# WaterSens_V1-0.net
KiCad netlist of a schematic drawn in EAGLE
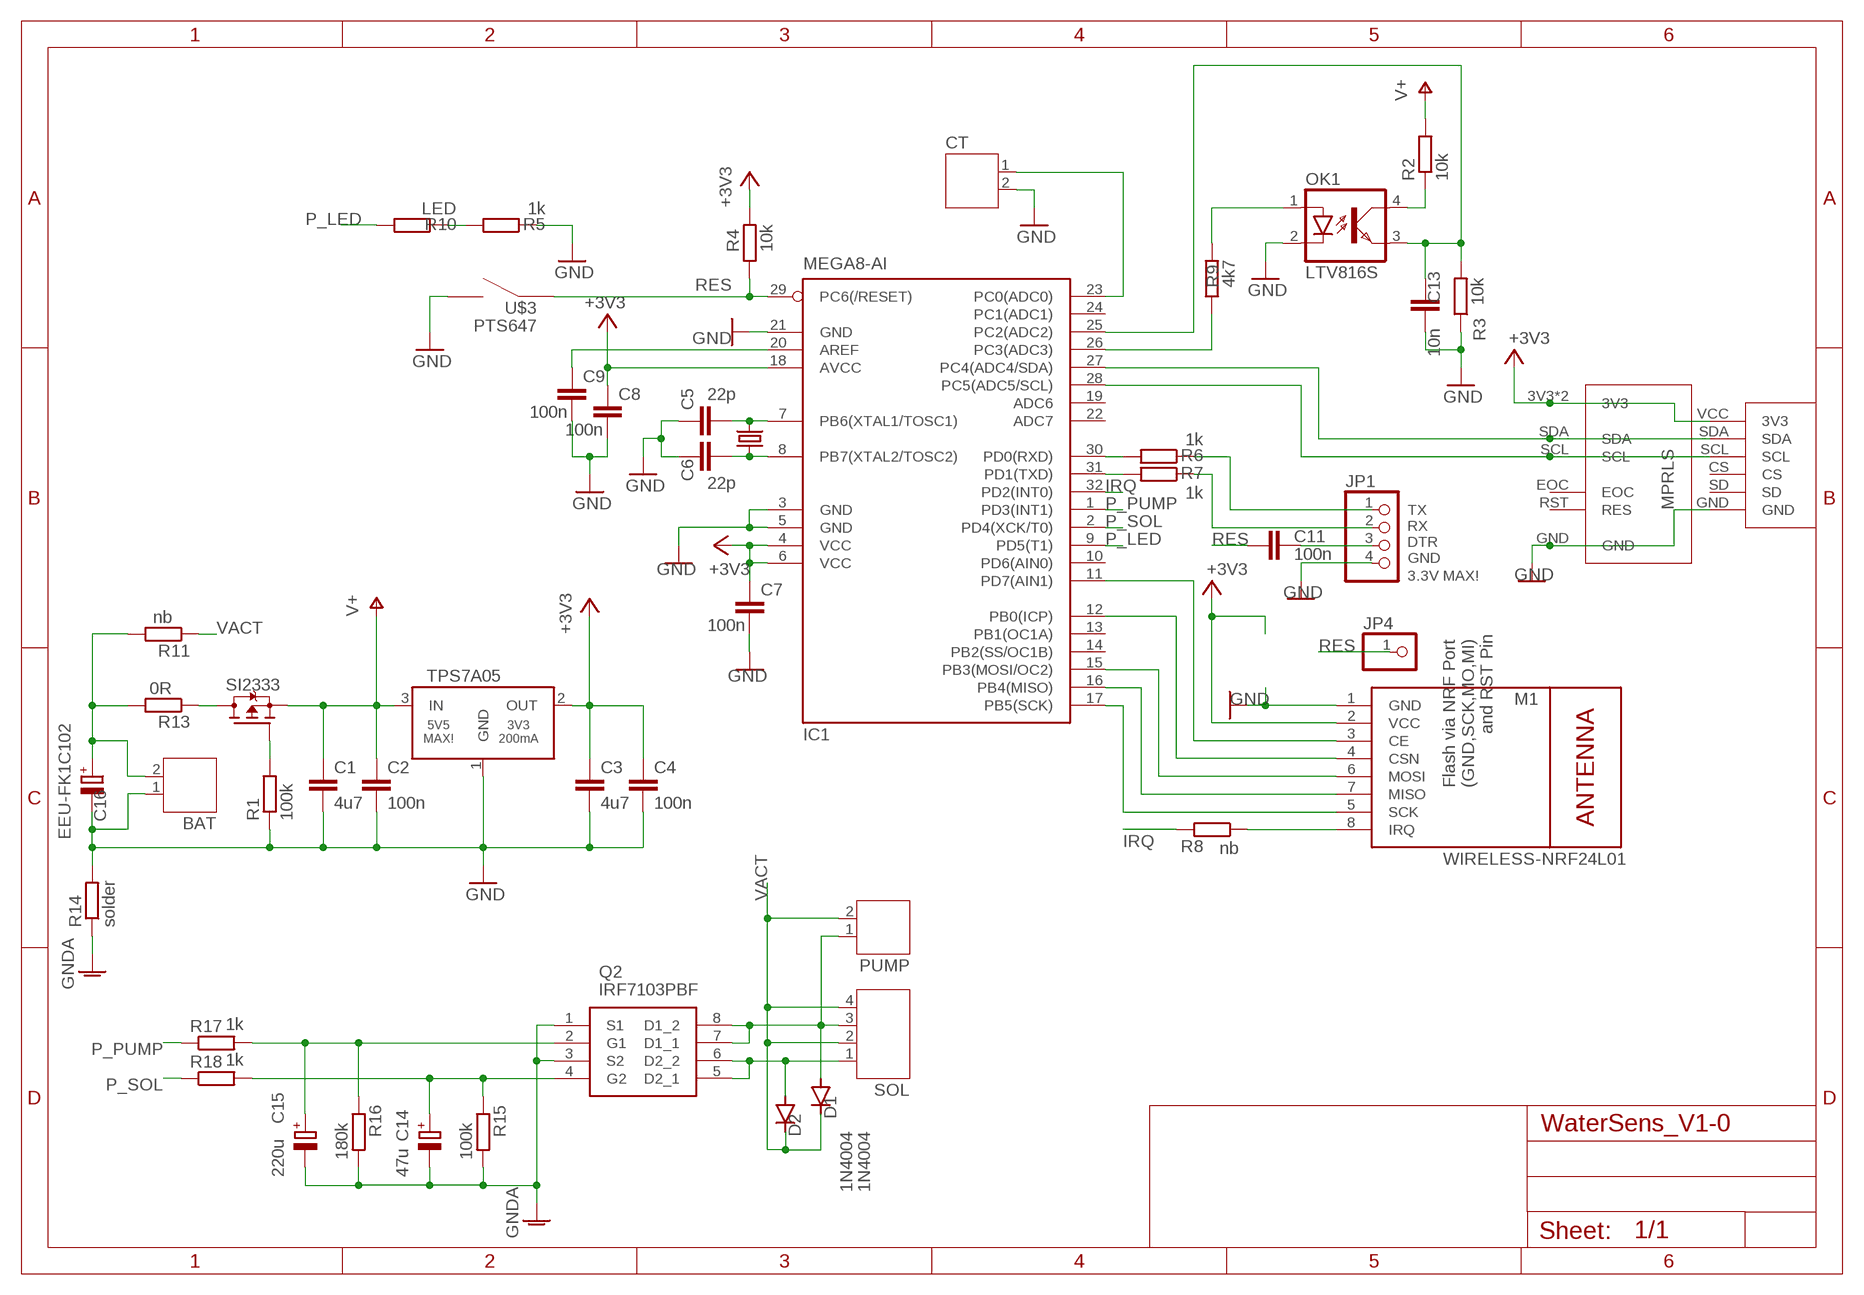
[diagram p0: schematic, sheet 1]

(export (version "E")
  (design (tool "Eeschema 10.0.6"))
  (components
    (comp (ref "BAT")
      (value "JST-PH2")
      (footprint "eagle-import:JST-PH2")
      (libsource (lib "eagle-import") (part "JST-PH2"))
    )
    (comp (ref "C1")
      (value "4u7")
      (footprint "eagle-import:C0805")
      (libsource (lib "eagle-import") (part "C-EUC0805"))
    )
    (comp (ref "C2")
      (value "100n")
      (footprint "eagle-import:C0805")
      (libsource (lib "eagle-import") (part "C-EUC0805"))
    )
    (comp (ref "C3")
      (value "4u7")
      (footprint "eagle-import:C0805")
      (libsource (lib "eagle-import") (part "C-EUC0805"))
    )
    (comp (ref "C4")
      (value "100n")
      (footprint "eagle-import:C0805")
      (libsource (lib "eagle-import") (part "C-EUC0805"))
    )
    (comp (ref "C5")
      (value "22p")
      (footprint "eagle-import:C0805")
      (libsource (lib "eagle-import") (part "C-EUC0805"))
    )
    (comp (ref "C6")
      (value "22p")
      (footprint "eagle-import:C0805")
      (libsource (lib "eagle-import") (part "C-EUC0805"))
    )
    (comp (ref "C7")
      (value "100n")
      (footprint "eagle-import:C0805")
      (libsource (lib "eagle-import") (part "C-EUC0805"))
    )
    (comp (ref "C8")
      (value "100n")
      (footprint "eagle-import:C0805")
      (libsource (lib "eagle-import") (part "C-EUC0805"))
    )
    (comp (ref "C9")
      (value "100n")
      (footprint "eagle-import:C0805")
      (libsource (lib "eagle-import") (part "C-EUC0805"))
    )
    (comp (ref "C11")
      (value "100n")
      (footprint "eagle-import:C0805")
      (libsource (lib "eagle-import") (part "C-EUC0805"))
    )
    (comp (ref "C13")
      (value "10n")
      (footprint "eagle-import:C0805")
      (libsource (lib "eagle-import") (part "C-EUC0805"))
    )
    (comp (ref "C14")
      (value "47u")
      (footprint "eagle-import:E1,8-4")
      (libsource (lib "eagle-import") (part "CPOL-EUE1.8-4"))
    )
    (comp (ref "C15")
      (value "220u")
      (footprint "eagle-import:E2,5-6E")
      (libsource (lib "eagle-import") (part "CPOL-EUE2,5-6E"))
    )
    (comp (ref "C16")
      (value "EEU-FK1C102")
      (footprint "eagle-import:E5-10,5")
      (libsource (lib "eagle-import") (part "CPOL-EUE5-10.5"))
    )
    (comp (ref "CT")
      (value "JST-PH2")
      (footprint "eagle-import:JST-PH2")
      (libsource (lib "eagle-import") (part "JST-PH2"))
    )
    (comp (ref "D1")
      (value "1N4004")
      (footprint "eagle-import:DO41-10")
      (libsource (lib "eagle-import") (part "1N4004"))
    )
    (comp (ref "D2")
      (value "1N4004")
      (footprint "eagle-import:DO41-10")
      (libsource (lib "eagle-import") (part "1N4004"))
    )
    (comp (ref "IC1")
      (value "MEGA8-AI")
      (footprint "eagle-import:TQFP32-08")
      (fields (field (name "MPN") "ATMEGA8-16AU"))
      (libsource (lib "eagle-import") (part "MEGA8-AI"))
    )
    (comp (ref "JP1")
      (value "PINHD-1X4")
      (footprint "eagle-import:1X04")
      (libsource (lib "eagle-import") (part "PINHD-1X4"))
    )
    (comp (ref "JP4")
      (value "PINHD-1X1")
      (footprint "eagle-import:1X01")
      (libsource (lib "eagle-import") (part "PINHD-1X1"))
    )
    (comp (ref "M1")
      (value "WIRELESS-NRF24L01")
      (footprint "eagle-import:WIRELESS-NRF24L01")
      (libsource (lib "eagle-import") (part "WIRELESS-NRF24L01"))
    )
    (comp (ref "OK1")
      (value "LTV816S")
      (footprint "eagle-import:DIL4-SMD")
      (libsource (lib "eagle-import") (part "LTV816S"))
    )
    (comp (ref "PUMP")
      (value "JST-PH2")
      (footprint "eagle-import:JST-PH2")
      (libsource (lib "eagle-import") (part "JST-PH2"))
    )
    (comp (ref "Q1")
      (value "CRYSTALHC49UP")
      (footprint "eagle-import:HC49UP")
      (libsource (lib "eagle-import") (part "CRYSTALHC49UP"))
    )
    (comp (ref "Q2")
      (value "IRF7103PBF")
      (footprint "eagle-import:SOIC127P600X175-8N")
      (libsource (lib "eagle-import") (part "IRF7103PBF"))
    )
    (comp (ref "R1")
      (value "100k")
      (footprint "eagle-import:R0805")
      (libsource (lib "eagle-import") (part "R-EU_R0805"))
    )
    (comp (ref "R2")
      (value "10k")
      (footprint "eagle-import:R0805")
      (libsource (lib "eagle-import") (part "R-EU_R0805"))
    )
    (comp (ref "R3")
      (value "10k")
      (footprint "eagle-import:R0805")
      (libsource (lib "eagle-import") (part "R-EU_R0805"))
    )
    (comp (ref "R4")
      (value "10k")
      (footprint "eagle-import:R0805")
      (libsource (lib "eagle-import") (part "R-EU_R0805"))
    )
    (comp (ref "R5")
      (value "1k")
      (footprint "eagle-import:R0805")
      (libsource (lib "eagle-import") (part "R-EU_R0805"))
    )
    (comp (ref "R6")
      (value "1k")
      (footprint "eagle-import:R0805")
      (libsource (lib "eagle-import") (part "R-EU_R0805"))
    )
    (comp (ref "R7")
      (value "1k")
      (footprint "eagle-import:R0805")
      (libsource (lib "eagle-import") (part "R-EU_R0805"))
    )
    (comp (ref "R8")
      (value "nb")
      (footprint "eagle-import:R0805")
      (libsource (lib "eagle-import") (part "R-EU_R0805"))
    )
    (comp (ref "R9")
      (value "4k7")
      (footprint "eagle-import:R0805")
      (libsource (lib "eagle-import") (part "R-EU_R0805"))
    )
    (comp (ref "R10")
      (value "LED")
      (footprint "eagle-import:R0805")
      (libsource (lib "eagle-import") (part "R-EU_R0805"))
    )
    (comp (ref "R11")
      (value "nb")
      (footprint "eagle-import:R0805")
      (libsource (lib "eagle-import") (part "R-EU_R0805"))
    )
    (comp (ref "R13")
      (value "0R")
      (footprint "eagle-import:R0805")
      (libsource (lib "eagle-import") (part "R-EU_R0805"))
    )
    (comp (ref "R14")
      (value "solder")
      (footprint "eagle-import:R0805")
      (libsource (lib "eagle-import") (part "R-EU_R0805"))
    )
    (comp (ref "R15")
      (value "100k")
      (footprint "eagle-import:R0805")
      (libsource (lib "eagle-import") (part "R-EU_R0805"))
    )
    (comp (ref "R16")
      (value "180k")
      (footprint "eagle-import:R0805")
      (libsource (lib "eagle-import") (part "R-EU_R0805"))
    )
    (comp (ref "R17")
      (value "1k")
      (footprint "eagle-import:R0805")
      (libsource (lib "eagle-import") (part "R-EU_R0805"))
    )
    (comp (ref "R18")
      (value "1k")
      (footprint "eagle-import:R0805")
      (libsource (lib "eagle-import") (part "R-EU_R0805"))
    )
    (comp (ref "SOL")
      (value "JST-PH4")
      (footprint "eagle-import:JST-PH4")
      (libsource (lib "eagle-import") (part "JST-PH4"))
    )
    (comp (ref "U$1")
      (value "MPRLS_ADA")
      (footprint "eagle-import:MPRLS_ADA")
      (libsource (lib "eagle-import") (part "MPRLS_ADA"))
    )
    (comp (ref "U$2")
      (value "TEMP-HUM-PRES-BME280-3V3")
      (footprint "eagle-import:TEMP-HUM-PRES-BME280-3V3")
      (libsource (lib "eagle-import") (part "TEMP-HUM-PRES-BME280-3V3"))
    )
    (comp (ref "U$3")
      (value "PTS647")
      (footprint "eagle-import:PTS647")
      (libsource (lib "eagle-import") (part "PTS647"))
    )
    (comp (ref "U$5")
      (value "TPS7A05")
      (footprint "eagle-import:SOT23")
      (libsource (lib "eagle-import") (part "TPS7A05"))
    )
    (comp (ref "U$6")
      (value "SI2333")
      (footprint "eagle-import:SOT23")
      (libsource (lib "eagle-import") (part "SI2333"))
    )
  )
  (nets
    (net (code "1") (name "+3V3") (class "Default")
      (node (ref "C3") (pin "1") (pinfunction "1_1") (pintype "passive"))
      (node (ref "C4") (pin "1") (pinfunction "1_1") (pintype "passive"))
      (node (ref "C7") (pin "1") (pinfunction "1_1") (pintype "passive"))
      (node (ref "C8") (pin "1") (pinfunction "1_1") (pintype "passive"))
      (node (ref "IC1") (pin "18") (pinfunction "AVCC_18") (pintype "power_in"))
      (node (ref "IC1") (pin "4") (pinfunction "VCC_4") (pintype "power_in"))
      (node (ref "IC1") (pin "6") (pinfunction "VCC_6") (pintype "power_in"))
      (node (ref "M1") (pin "2") (pinfunction "VCC_2") (pintype "power_in"))
      (node (ref "R4") (pin "2") (pinfunction "2_2") (pintype "passive"))
      (node (ref "U$1") (pin "3V3") (pinfunction "3V3_3V3") (pintype "bidirectional"))
      (node (ref "U$1") (pin "VIN") (pinfunction "3V3_VIN") (pintype "bidirectional"))
      (node (ref "U$2") (pin "VCC") (pinfunction "3V3_VCC") (pintype "bidirectional"))
      (node (ref "U$5") (pin "2") (pinfunction "OUT_2") (pintype "bidirectional"))
    )
    (net (code "2") (name "/IRQ") (class "Default")
      (node (ref "IC1") (pin "32") (pinfunction "PD2(INT0)_32") (pintype "bidirectional"))
      (node (ref "R8") (pin "2") (pinfunction "2_2") (pintype "passive"))
    )
    (net (code "3") (name "/P_LED") (class "Default")
      (node (ref "IC1") (pin "9") (pinfunction "PD5(T1)_9") (pintype "bidirectional"))
      (node (ref "R10") (pin "2") (pinfunction "2_2") (pintype "passive"))
    )
    (net (code "4") (name "/P_PUMP") (class "Default")
      (node (ref "IC1") (pin "1") (pinfunction "PD3(INT1)_1") (pintype "bidirectional"))
      (node (ref "R17") (pin "1") (pinfunction "1_1") (pintype "passive"))
    )
    (net (code "5") (name "/P_SOL") (class "Default")
      (node (ref "IC1") (pin "2") (pinfunction "PD4(XCK/T0)_2") (pintype "bidirectional"))
      (node (ref "R18") (pin "1") (pinfunction "1_1") (pintype "passive"))
    )
    (net (code "6") (name "/RES") (class "Default")
      (node (ref "C11") (pin "1") (pinfunction "1_1") (pintype "passive"))
      (node (ref "IC1") (pin "29") (pinfunction "PC6(/RESET)_29") (pintype "bidirectional"))
      (node (ref "JP4") (pin "1") (pinfunction "1_1") (pintype "passive"))
      (node (ref "R4") (pin "1") (pinfunction "1_1") (pintype "passive"))
      (node (ref "U$3") (pin "1") (pinfunction "P$1_1") (pintype "bidirectional"))
      (node (ref "U$3") (pin "2") (pinfunction "P$1_2") (pintype "bidirectional"))
    )
    (net (code "7") (name "/VACT") (class "Default")
      (node (ref "D1") (pin "C") (pinfunction "C_C") (pintype "passive"))
      (node (ref "D2") (pin "C") (pinfunction "C_C") (pintype "passive"))
      (node (ref "PUMP") (pin "2") (pinfunction "2_2") (pintype "passive"))
      (node (ref "R11") (pin "1") (pinfunction "1_1") (pintype "passive"))
      (node (ref "SOL") (pin "2") (pinfunction "2_2") (pintype "passive"))
      (node (ref "SOL") (pin "4") (pinfunction "4_4") (pintype "passive"))
    )
    (net (code "8") (name "GND") (class "Default")
      (node (ref "BAT") (pin "1") (pinfunction "1_1") (pintype "passive"))
      (node (ref "C1") (pin "2") (pinfunction "2_2") (pintype "passive"))
      (node (ref "C13") (pin "1") (pinfunction "1_1") (pintype "passive"))
      (node (ref "C16") (pin "-") (pinfunction "-_-") (pintype "passive"))
      (node (ref "C2") (pin "2") (pinfunction "2_2") (pintype "passive"))
      (node (ref "C3") (pin "2") (pinfunction "2_2") (pintype "passive"))
      (node (ref "C4") (pin "2") (pinfunction "2_2") (pintype "passive"))
      (node (ref "C5") (pin "1") (pinfunction "1_1") (pintype "passive"))
      (node (ref "C6") (pin "1") (pinfunction "1_1") (pintype "passive"))
      (node (ref "C7") (pin "2") (pinfunction "2_2") (pintype "passive"))
      (node (ref "C8") (pin "2") (pinfunction "2_2") (pintype "passive"))
      (node (ref "C9") (pin "2") (pinfunction "2_2") (pintype "passive"))
      (node (ref "CT") (pin "2") (pinfunction "2_2") (pintype "passive"))
      (node (ref "IC1") (pin "21") (pinfunction "GND_21") (pintype "power_in"))
      (node (ref "IC1") (pin "3") (pinfunction "GND_3") (pintype "power_in"))
      (node (ref "IC1") (pin "5") (pinfunction "GND_5") (pintype "power_in"))
      (node (ref "JP1") (pin "4") (pinfunction "4_4") (pintype "passive"))
      (node (ref "M1") (pin "1") (pinfunction "GND_1") (pintype "power_in"))
      (node (ref "OK1") (pin "2") (pinfunction "C_2") (pintype "passive"))
      (node (ref "R1") (pin "1") (pinfunction "1_1") (pintype "passive"))
      (node (ref "R14") (pin "2") (pinfunction "2_2") (pintype "passive"))
      (node (ref "R3") (pin "1") (pinfunction "1_1") (pintype "passive"))
      (node (ref "R5") (pin "1") (pinfunction "1_1") (pintype "passive"))
      (node (ref "U$1") (pin "GND") (pinfunction "GND_GND") (pintype "bidirectional"))
      (node (ref "U$2") (pin "GND") (pinfunction "GND_GND") (pintype "bidirectional"))
      (node (ref "U$3") (pin "3") (pinfunction "P$2_3") (pintype "bidirectional"))
      (node (ref "U$3") (pin "4") (pinfunction "P$2_4") (pintype "bidirectional"))
      (node (ref "U$5") (pin "1") (pinfunction "GND_1") (pintype "bidirectional"))
    )
    (net (code "9") (name "GNDA") (class "Default")
      (node (ref "C14") (pin "-") (pinfunction "-_-") (pintype "passive"))
      (node (ref "C15") (pin "-") (pinfunction "-_-") (pintype "passive"))
      (node (ref "Q2") (pin "1") (pinfunction "S1_1") (pintype "bidirectional"))
      (node (ref "Q2") (pin "3") (pinfunction "S2_3") (pintype "bidirectional"))
      (node (ref "R14") (pin "1") (pinfunction "1_1") (pintype "passive"))
      (node (ref "R15") (pin "2") (pinfunction "2_2") (pintype "passive"))
      (node (ref "R16") (pin "2") (pinfunction "2_2") (pintype "passive"))
    )
    (net (code "10") (name "Net-(BAT-Pad2)") (class "Default")
      (node (ref "BAT") (pin "2") (pinfunction "2_2") (pintype "passive"))
      (node (ref "C16") (pin "+") (pinfunction "+_+") (pintype "passive"))
      (node (ref "R11") (pin "2") (pinfunction "2_2") (pintype "passive"))
      (node (ref "R13") (pin "2") (pinfunction "2_2") (pintype "passive"))
    )
    (net (code "11") (name "Net-(C11-Pad2)") (class "Default")
      (node (ref "C11") (pin "2") (pinfunction "2_2") (pintype "passive"))
      (node (ref "JP1") (pin "3") (pinfunction "3_3") (pintype "passive"))
    )
    (net (code "12") (name "Net-(IC1-AREF)") (class "Default")
      (node (ref "C9") (pin "1") (pinfunction "1_1") (pintype "passive"))
      (node (ref "IC1") (pin "20") (pinfunction "AREF_20") (pintype "passive"))
    )
    (net (code "13") (name "Net-(IC1-PB0(ICP))") (class "Default")
      (node (ref "IC1") (pin "12") (pinfunction "PB0(ICP)_12") (pintype "bidirectional"))
      (node (ref "M1") (pin "4") (pinfunction "CSN_4") (pintype "bidirectional"))
    )
    (net (code "14") (name "Net-(IC1-PB3(MOSI{slash}OC2))") (class "Default")
      (node (ref "IC1") (pin "15") (pinfunction "PB3(MOSI/OC2)_15") (pintype "bidirectional"))
      (node (ref "M1") (pin "6") (pinfunction "MOSI_6") (pintype "bidirectional"))
    )
    (net (code "15") (name "Net-(IC1-PB4(MISO))") (class "Default")
      (node (ref "IC1") (pin "16") (pinfunction "PB4(MISO)_16") (pintype "bidirectional"))
      (node (ref "M1") (pin "7") (pinfunction "MISO_7") (pintype "bidirectional"))
    )
    (net (code "16") (name "Net-(IC1-PB5(SCK))") (class "Default")
      (node (ref "IC1") (pin "17") (pinfunction "PB5(SCK)_17") (pintype "bidirectional"))
      (node (ref "M1") (pin "5") (pinfunction "SCK_5") (pintype "bidirectional"))
    )
    (net (code "17") (name "Net-(IC1-PB6(XTAL1{slash}TOSC1))") (class "Default")
      (node (ref "C5") (pin "2") (pinfunction "2_2") (pintype "passive"))
      (node (ref "IC1") (pin "7") (pinfunction "PB6(XTAL1/TOSC1)_7") (pintype "bidirectional"))
      (node (ref "Q1") (pin "2") (pinfunction "2_2") (pintype "passive"))
    )
    (net (code "18") (name "Net-(IC1-PB7(XTAL2{slash}TOSC2))") (class "Default")
      (node (ref "C6") (pin "2") (pinfunction "2_2") (pintype "passive"))
      (node (ref "IC1") (pin "8") (pinfunction "PB7(XTAL2/TOSC2)_8") (pintype "bidirectional"))
      (node (ref "Q1") (pin "1") (pinfunction "1_1") (pintype "passive"))
    )
    (net (code "19") (name "Net-(IC1-PC0(ADC0))") (class "Default")
      (node (ref "CT") (pin "1") (pinfunction "1_1") (pintype "passive"))
      (node (ref "IC1") (pin "23") (pinfunction "PC0(ADC0)_23") (pintype "bidirectional"))
    )
    (net (code "20") (name "Net-(IC1-PC2(ADC2))") (class "Default")
      (node (ref "C13") (pin "2") (pinfunction "2_2") (pintype "passive"))
      (node (ref "IC1") (pin "25") (pinfunction "PC2(ADC2)_25") (pintype "bidirectional"))
      (node (ref "OK1") (pin "3") (pinfunction "EMIT_3") (pintype "passive"))
      (node (ref "R3") (pin "2") (pinfunction "2_2") (pintype "passive"))
    )
    (net (code "21") (name "Net-(IC1-PC3(ADC3))") (class "Default")
      (node (ref "IC1") (pin "26") (pinfunction "PC3(ADC3)_26") (pintype "bidirectional"))
      (node (ref "R9") (pin "1") (pinfunction "1_1") (pintype "passive"))
    )
    (net (code "22") (name "Net-(IC1-PC4(ADC4{slash}SDA))") (class "Default")
      (node (ref "IC1") (pin "27") (pinfunction "PC4(ADC4/SDA)_27") (pintype "bidirectional"))
      (node (ref "U$1") (pin "SDA") (pinfunction "SDA_SDA") (pintype "bidirectional"))
      (node (ref "U$2") (pin "SDA") (pinfunction "SDA_SDA") (pintype "bidirectional"))
    )
    (net (code "23") (name "Net-(IC1-PC5(ADC5{slash}SCL))") (class "Default")
      (node (ref "IC1") (pin "28") (pinfunction "PC5(ADC5/SCL)_28") (pintype "bidirectional"))
      (node (ref "U$1") (pin "SCL") (pinfunction "SCL_SCL") (pintype "bidirectional"))
      (node (ref "U$2") (pin "SCL") (pinfunction "SCL_SCL") (pintype "bidirectional"))
    )
    (net (code "24") (name "Net-(IC1-PD0(RXD))") (class "Default")
      (node (ref "IC1") (pin "30") (pinfunction "PD0(RXD)_30") (pintype "bidirectional"))
      (node (ref "R6") (pin "2") (pinfunction "2_2") (pintype "passive"))
    )
    (net (code "25") (name "Net-(IC1-PD1(TXD))") (class "Default")
      (node (ref "IC1") (pin "31") (pinfunction "PD1(TXD)_31") (pintype "bidirectional"))
      (node (ref "R7") (pin "2") (pinfunction "2_2") (pintype "passive"))
    )
    (net (code "26") (name "Net-(IC1-PD7(AIN1))") (class "Default")
      (node (ref "IC1") (pin "11") (pinfunction "PD7(AIN1)_11") (pintype "bidirectional"))
      (node (ref "M1") (pin "3") (pinfunction "CE_3") (pintype "bidirectional"))
    )
    (net (code "27") (name "Net-(JP1-Pad1)") (class "Default")
      (node (ref "JP1") (pin "1") (pinfunction "1_1") (pintype "passive"))
      (node (ref "R6") (pin "1") (pinfunction "1_1") (pintype "passive"))
    )
    (net (code "28") (name "Net-(JP1-Pad2)") (class "Default")
      (node (ref "JP1") (pin "2") (pinfunction "2_2") (pintype "passive"))
      (node (ref "R7") (pin "1") (pinfunction "1_1") (pintype "passive"))
    )
    (net (code "29") (name "Net-(M1-IRQ)") (class "Default")
      (node (ref "M1") (pin "8") (pinfunction "IRQ_8") (pintype "bidirectional"))
      (node (ref "R8") (pin "1") (pinfunction "1_1") (pintype "passive"))
    )
    (net (code "30") (name "Net-(OK1-A)") (class "Default")
      (node (ref "OK1") (pin "1") (pinfunction "A_1") (pintype "passive"))
      (node (ref "R9") (pin "2") (pinfunction "2_2") (pintype "passive"))
    )
    (net (code "31") (name "Net-(OK1-COL)") (class "Default")
      (node (ref "OK1") (pin "4") (pinfunction "COL_4") (pintype "passive"))
      (node (ref "R2") (pin "1") (pinfunction "1_1") (pintype "passive"))
    )
    (net (code "32") (name "Net-(Q2-D1_1)") (class "Default")
      (node (ref "D1") (pin "A") (pinfunction "A_A") (pintype "passive"))
      (node (ref "PUMP") (pin "1") (pinfunction "1_1") (pintype "passive"))
      (node (ref "Q2") (pin "7") (pinfunction "D1_1_7") (pintype "bidirectional"))
      (node (ref "Q2") (pin "8") (pinfunction "D1_2_8") (pintype "bidirectional"))
      (node (ref "SOL") (pin "3") (pinfunction "3_3") (pintype "passive"))
    )
    (net (code "33") (name "Net-(Q2-D2_1)") (class "Default")
      (node (ref "D2") (pin "A") (pinfunction "A_A") (pintype "passive"))
      (node (ref "Q2") (pin "5") (pinfunction "D2_1_5") (pintype "bidirectional"))
      (node (ref "Q2") (pin "6") (pinfunction "D2_2_6") (pintype "bidirectional"))
      (node (ref "SOL") (pin "1") (pinfunction "1_1") (pintype "passive"))
    )
    (net (code "34") (name "Net-(Q2-G1)") (class "Default")
      (node (ref "C15") (pin "+") (pinfunction "+_+") (pintype "passive"))
      (node (ref "Q2") (pin "2") (pinfunction "G1_2") (pintype "bidirectional"))
      (node (ref "R16") (pin "1") (pinfunction "1_1") (pintype "passive"))
      (node (ref "R17") (pin "2") (pinfunction "2_2") (pintype "passive"))
    )
    (net (code "35") (name "Net-(Q2-G2)") (class "Default")
      (node (ref "C14") (pin "+") (pinfunction "+_+") (pintype "passive"))
      (node (ref "Q2") (pin "4") (pinfunction "G2_4") (pintype "bidirectional"))
      (node (ref "R15") (pin "1") (pinfunction "1_1") (pintype "passive"))
      (node (ref "R18") (pin "2") (pinfunction "2_2") (pintype "passive"))
    )
    (net (code "36") (name "Net-(R10-Pad1)") (class "Default")
      (node (ref "R10") (pin "1") (pinfunction "1_1") (pintype "passive"))
      (node (ref "R5") (pin "2") (pinfunction "2_2") (pintype "passive"))
    )
    (net (code "37") (name "Net-(U$6-D)") (class "Default")
      (node (ref "R13") (pin "1") (pinfunction "1_1") (pintype "passive"))
      (node (ref "U$6") (pin "3") (pinfunction "D_3") (pintype "passive"))
    )
    (net (code "38") (name "Net-(U$6-G)") (class "Default")
      (node (ref "R1") (pin "2") (pinfunction "2_2") (pintype "passive"))
      (node (ref "U$6") (pin "1") (pinfunction "G_1") (pintype "passive"))
    )
    (net (code "39") (name "V+") (class "Default")
      (node (ref "C1") (pin "1") (pinfunction "1_1") (pintype "passive"))
      (node (ref "C2") (pin "1") (pinfunction "1_1") (pintype "passive"))
      (node (ref "R2") (pin "2") (pinfunction "2_2") (pintype "passive"))
      (node (ref "U$5") (pin "3") (pinfunction "IN_3") (pintype "bidirectional"))
      (node (ref "U$6") (pin "2") (pinfunction "S_2") (pintype "passive"))
    )
    (net (code "40") (name "unconnected-(IC1-ADC6-Pad19)") (class "Default")
      (node (ref "IC1") (pin "19") (pinfunction "ADC6_19") (pintype "bidirectional"))
    )
    (net (code "41") (name "unconnected-(IC1-ADC7-Pad22)") (class "Default")
      (node (ref "IC1") (pin "22") (pinfunction "ADC7_22") (pintype "bidirectional"))
    )
    (net (code "42") (name "unconnected-(IC1-PB1(OC1A)-Pad13)") (class "Default")
      (node (ref "IC1") (pin "13") (pinfunction "PB1(OC1A)_13") (pintype "bidirectional"))
    )
    (net (code "43") (name "unconnected-(IC1-PB2(SS{slash}OC1B)-Pad14)") (class "Default")
      (node (ref "IC1") (pin "14") (pinfunction "PB2(SS/OC1B)_14") (pintype "bidirectional"))
    )
    (net (code "44") (name "unconnected-(IC1-PC1(ADC1)-Pad24)") (class "Default")
      (node (ref "IC1") (pin "24") (pinfunction "PC1(ADC1)_24") (pintype "bidirectional"))
    )
    (net (code "45") (name "unconnected-(IC1-PD6(AIN0)-Pad10)") (class "Default")
      (node (ref "IC1") (pin "10") (pinfunction "PD6(AIN0)_10") (pintype "bidirectional"))
    )
    (net (code "46") (name "unconnected-(U$1-PadEOC)") (class "Default")
      (node (ref "U$1") (pin "EOC") (pinfunction "EOC_EOC") (pintype "bidirectional"))
    )
    (net (code "47") (name "unconnected-(U$1-RES-PadRST)") (class "Default")
      (node (ref "U$1") (pin "RST") (pinfunction "RES_RST") (pintype "bidirectional"))
    )
    (net (code "48") (name "unconnected-(U$2-PadCS)") (class "Default")
      (node (ref "U$2") (pin "CS") (pinfunction "CS_CS") (pintype "bidirectional"))
    )
    (net (code "49") (name "unconnected-(U$2-PadSD)") (class "Default")
      (node (ref "U$2") (pin "SD") (pinfunction "SD_SD") (pintype "bidirectional"))
    )
  )
)
